# ProProject_Access_Control_USB_Adapter_20.net
KiCad netlist of a schematic drawn in EasyEDA Pro
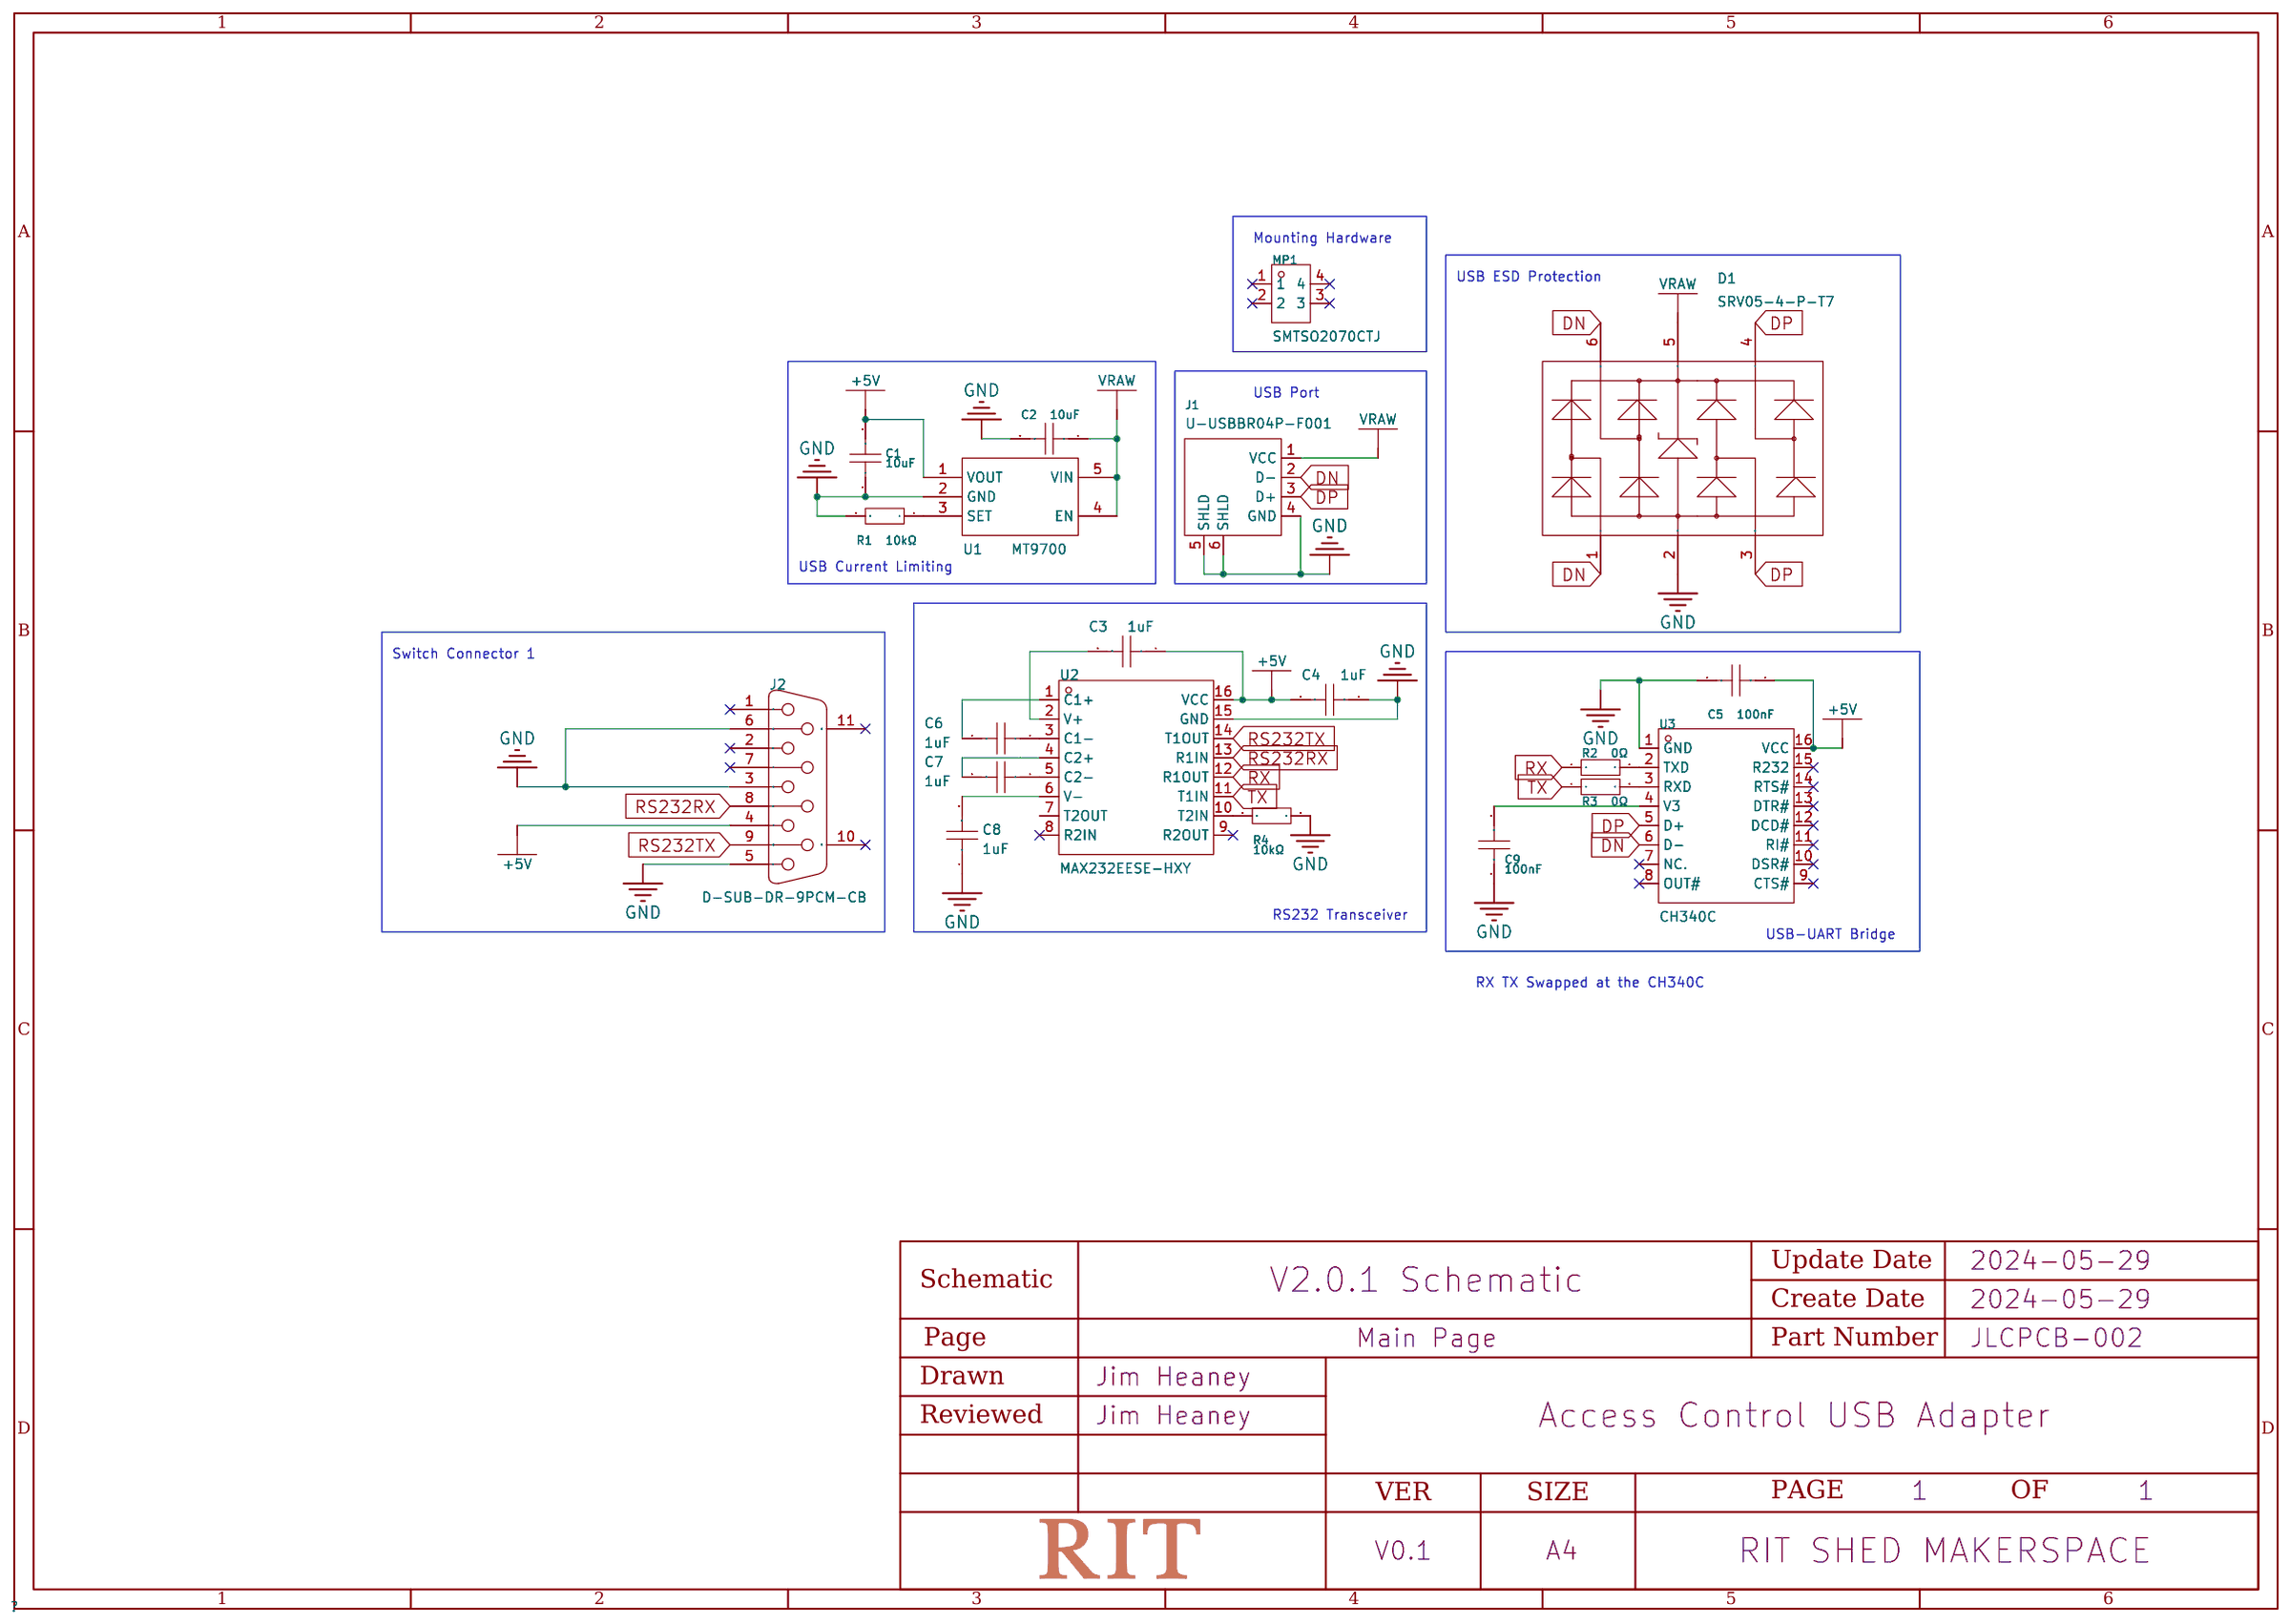
[diagram p0: schematic sheet]

(export (version "E")
  (design (tool "Eeschema 10.0.6"))
  (components
    (comp (ref "C1")
      (value "10uF")
      (footprint "easyedapro:C0603")
      (fields
        (field (name "Manufacturer Part") "CL10A106MA8NRNC")
        (field (name "Manufacturer") "SAMSUNG(三星)")
      )
      (libsource (lib "easyedapro") (part "CL10A106MA8NRNC"))
    )
    (comp (ref "C2")
      (value "10uF")
      (footprint "easyedapro:C0603")
      (fields
        (field (name "Manufacturer Part") "CL10A106MA8NRNC")
        (field (name "Manufacturer") "SAMSUNG(三星)")
      )
      (libsource (lib "easyedapro") (part "CL10A106MA8NRNC"))
    )
    (comp (ref "C3")
      (value "1uF")
      (footprint "easyedapro:C0603")
      (fields
        (field (name "Manufacturer Part") "CL10A105KB8NNNC")
        (field (name "Manufacturer") "SAMSUNG(三星)")
      )
      (libsource (lib "easyedapro") (part "CL10A105KB8NNNC"))
    )
    (comp (ref "C4")
      (value "1uF")
      (footprint "easyedapro:C0603")
      (fields
        (field (name "Manufacturer Part") "CL10A105KB8NNNC")
        (field (name "Manufacturer") "SAMSUNG(三星)")
      )
      (libsource (lib "easyedapro") (part "CL10A105KB8NNNC"))
    )
    (comp (ref "C5")
      (value "100nF")
      (footprint "easyedapro:C0603")
      (fields
        (field (name "Manufacturer Part") "CC0603KRX7R9BB104")
        (field (name "Manufacturer") "YAGEO(国巨)")
      )
      (libsource (lib "easyedapro") (part "CC0603KRX7R9BB104"))
    )
    (comp (ref "C6")
      (value "1uF")
      (footprint "easyedapro:C0603")
      (fields
        (field (name "Manufacturer Part") "CL10A105KB8NNNC")
        (field (name "Manufacturer") "SAMSUNG(三星)")
      )
      (libsource (lib "easyedapro") (part "CL10A105KB8NNNC"))
    )
    (comp (ref "C7")
      (value "1uF")
      (footprint "easyedapro:C0603")
      (fields
        (field (name "Manufacturer Part") "CL10A105KB8NNNC")
        (field (name "Manufacturer") "SAMSUNG(三星)")
      )
      (libsource (lib "easyedapro") (part "CL10A105KB8NNNC"))
    )
    (comp (ref "C8")
      (value "1uF")
      (footprint "easyedapro:C0603")
      (fields
        (field (name "Manufacturer Part") "CL10A105KB8NNNC")
        (field (name "Manufacturer") "SAMSUNG(三星)")
      )
      (libsource (lib "easyedapro") (part "CL10A105KB8NNNC"))
    )
    (comp (ref "C9")
      (value "100nF")
      (footprint "easyedapro:C0603")
      (fields
        (field (name "Manufacturer Part") "CC0603KRX7R9BB104")
        (field (name "Manufacturer") "YAGEO(国巨)")
      )
      (libsource (lib "easyedapro") (part "CC0603KRX7R9BB104"))
    )
    (comp (ref "D1")
      (value "SRV05-4-P-T7")
      (footprint "easyedapro:SOT-23-6_L2.9-W1.6-P0.95-LS2.8-BR")
      (fields (field (name "Manufacturer") "PROTEK"))
      (libsource (lib "easyedapro") (part "SRV05-4-P-T7"))
    )
    (comp (ref "J1")
      (value "U-USBBR04P-F001")
      (footprint "easyedapro:USB-B-TH_U241-041N-1BR85-1")
      (fields (field (name "Manufacturer") "Ckmtw(灿科盟)"))
      (libsource (lib "easyedapro") (part "U-USBBR04P-F001"))
    )
    (comp (ref "J2")
      (value "D-SUB-DR-9PCM-CB")
      (footprint "easyedapro:DB9-TH_ID09S33E4GV00LF")
      (fields (field (name "Manufacturer") "XUNPU(讯普)"))
      (libsource (lib "easyedapro") (part "D-SUB-DR-9PCM-CB"))
    )
    (comp (ref "MP1")
      (value "SMTSO2070CTJ")
      (footprint "easyedapro:SMD_BD5.6-L5.6-W5.6-D3.6")
      (fields (field (name "Manufacturer") "Sinhoo(雄和远景)"))
      (libsource (lib "easyedapro") (part "SMTSO2070CTJ"))
    )
    (comp (ref "R1")
      (value "10kΩ")
      (footprint "easyedapro:R0603")
      (fields
        (field (name "Manufacturer Part") "0603WAF1002T5E")
        (field (name "Manufacturer") "UNI-ROYAL(厚声)")
      )
      (libsource (lib "easyedapro") (part "0603WAF1002T5E"))
    )
    (comp (ref "R2")
      (value "0Ω")
      (footprint "easyedapro:R1206")
      (fields
        (field (name "Manufacturer Part") "1206W4F0000T5E")
        (field (name "Manufacturer") "UNI-ROYAL(厚声)")
      )
      (libsource (lib "easyedapro") (part "1206W4F0000T5E"))
    )
    (comp (ref "R3")
      (value "0Ω")
      (footprint "easyedapro:R1206")
      (fields
        (field (name "Manufacturer Part") "1206W4F0000T5E")
        (field (name "Manufacturer") "UNI-ROYAL(厚声)")
      )
      (libsource (lib "easyedapro") (part "1206W4F0000T5E"))
    )
    (comp (ref "R4")
      (value "10kΩ")
      (footprint "easyedapro:R0603")
      (fields
        (field (name "Manufacturer Part") "0603WAF1002T5E")
        (field (name "Manufacturer") "UNI-ROYAL(厚声)")
      )
      (libsource (lib "easyedapro") (part "0603WAF1002T5E"))
    )
    (comp (ref "U1")
      (value "MT9700")
      (footprint "easyedapro:SOT-23-5_L3.0-W1.7-P0.95-LS2.8-BR")
      (fields (field (name "Manufacturer") "西安航天民芯"))
      (libsource (lib "easyedapro") (part "MT9700"))
    )
    (comp (ref "U2")
      (value "MAX232EESE-HXY")
      (footprint "easyedapro:SOP-16_L9.9-W3.9-P1.27-LS6.0-BL")
      (description "Driver/receiver:2/2 Data Rate:120Kbps Data Rate:120Kbps Supply Voltage:5V Supply Voltage:5V")
      (fields (field (name "Manufacturer") "HXY MOSFET(华轩阳电子)"))
      (libsource (lib "easyedapro") (part "MAX232EESE-HXY"))
    )
    (comp (ref "U3")
      (value "CH340C")
      (footprint "easyedapro:SOP-16_L10.0-W3.9-P1.27-LS6.0-BL")
      (fields (field (name "Manufacturer") "WCH(南京沁恒)"))
      (libsource (lib "easyedapro") (part "CH340C"))
    )
  )
  (nets
    (net (code "1") (name "+5V") (class "Default")
      (node (ref "C1") (pin "2") (pinfunction "2_2") (pintype "input"))
      (node (ref "C3") (pin "1") (pinfunction "1_1") (pintype "unspecified"))
      (node (ref "C4") (pin "2") (pinfunction "2_2") (pintype "unspecified"))
      (node (ref "C5") (pin "2") (pinfunction "2_2") (pintype "input"))
      (node (ref "J2") (pin "4") (pinfunction "4_4") (pintype "input"))
      (node (ref "U1") (pin "1") (pinfunction "VOUT_1") (pintype "unspecified"))
      (node (ref "U2") (pin "16") (pinfunction "VCC_16") (pintype "unspecified"))
      (node (ref "U3") (pin "16") (pinfunction "VCC_16") (pintype "input"))
    )
    (net (code "2") (name "DN") (class "Default")
      (node (ref "D1") (pin "1") (pinfunction "1_1") (pintype "input"))
      (node (ref "D1") (pin "6") (pinfunction "6_6") (pintype "input"))
      (node (ref "J1") (pin "2") (pinfunction "D-_2") (pintype "input"))
      (node (ref "U3") (pin "6") (pinfunction "D-_6") (pintype "input"))
    )
    (net (code "3") (name "DP") (class "Default")
      (node (ref "D1") (pin "3") (pinfunction "3_3") (pintype "input"))
      (node (ref "D1") (pin "4") (pinfunction "4_4") (pintype "input"))
      (node (ref "J1") (pin "3") (pinfunction "D+_3") (pintype "input"))
      (node (ref "U3") (pin "5") (pinfunction "D+_5") (pintype "input"))
    )
    (net (code "4") (name "GND") (class "Default")
      (node (ref "C1") (pin "1") (pinfunction "1_1") (pintype "input"))
      (node (ref "C2") (pin "2") (pinfunction "2_2") (pintype "input"))
      (node (ref "C4") (pin "1") (pinfunction "1_1") (pintype "unspecified"))
      (node (ref "C5") (pin "1") (pinfunction "1_1") (pintype "input"))
      (node (ref "C8") (pin "1") (pinfunction "1_1") (pintype "unspecified"))
      (node (ref "C9") (pin "1") (pinfunction "1_1") (pintype "input"))
      (node (ref "D1") (pin "2") (pinfunction "2_2") (pintype "input"))
      (node (ref "J1") (pin "4") (pinfunction "GND_4") (pintype "input"))
      (node (ref "J1") (pin "5") (pinfunction "SHLD_5") (pintype "input"))
      (node (ref "J1") (pin "6") (pinfunction "SHLD_6") (pintype "input"))
      (node (ref "J2") (pin "3") (pinfunction "3_3") (pintype "input"))
      (node (ref "J2") (pin "5") (pinfunction "5_5") (pintype "input"))
      (node (ref "J2") (pin "6") (pinfunction "6_6") (pintype "input"))
      (node (ref "R1") (pin "2") (pinfunction "2_2") (pintype "input"))
      (node (ref "R4") (pin "1") (pinfunction "1_1") (pintype "input"))
      (node (ref "U1") (pin "2") (pinfunction "GND_2") (pintype "unspecified"))
      (node (ref "U2") (pin "15") (pinfunction "GND_15") (pintype "unspecified"))
      (node (ref "U3") (pin "1") (pinfunction "GND_1") (pintype "input"))
    )
    (net (code "5") (name "Net-(U1-SET)") (class "Default")
      (node (ref "R1") (pin "1") (pinfunction "1_1") (pintype "input"))
      (node (ref "U1") (pin "3") (pinfunction "SET_3") (pintype "unspecified"))
    )
    (net (code "6") (name "Net-(U2-C1+)") (class "Default")
      (node (ref "C6") (pin "2") (pinfunction "2_2") (pintype "unspecified"))
      (node (ref "U2") (pin "1") (pinfunction "C1+_1") (pintype "unspecified"))
    )
    (net (code "7") (name "Net-(U2-C1-)") (class "Default")
      (node (ref "C6") (pin "1") (pinfunction "1_1") (pintype "unspecified"))
      (node (ref "U2") (pin "3") (pinfunction "C1-_3") (pintype "unspecified"))
    )
    (net (code "8") (name "Net-(U2-C2+)") (class "Default")
      (node (ref "C7") (pin "2") (pinfunction "2_2") (pintype "unspecified"))
      (node (ref "U2") (pin "4") (pinfunction "C2+_4") (pintype "unspecified"))
    )
    (net (code "9") (name "Net-(U2-C2-)") (class "Default")
      (node (ref "C7") (pin "1") (pinfunction "1_1") (pintype "unspecified"))
      (node (ref "U2") (pin "5") (pinfunction "C2-_5") (pintype "unspecified"))
    )
    (net (code "10") (name "Net-(U2-T2IN)") (class "Default")
      (node (ref "R4") (pin "2") (pinfunction "2_2") (pintype "input"))
      (node (ref "U2") (pin "10") (pinfunction "T2IN_10") (pintype "unspecified"))
    )
    (net (code "11") (name "Net-(U2-V+)") (class "Default")
      (node (ref "C3") (pin "2") (pinfunction "2_2") (pintype "unspecified"))
      (node (ref "U2") (pin "2") (pinfunction "V+_2") (pintype "unspecified"))
    )
    (net (code "12") (name "Net-(U2-V-)") (class "Default")
      (node (ref "C8") (pin "2") (pinfunction "2_2") (pintype "unspecified"))
      (node (ref "U2") (pin "6") (pinfunction "V-_6") (pintype "unspecified"))
    )
    (net (code "13") (name "Net-(U3-RXD)") (class "Default")
      (node (ref "R3") (pin "2") (pinfunction "2_2") (pintype "input"))
      (node (ref "U3") (pin "3") (pinfunction "RXD_3") (pintype "input"))
    )
    (net (code "14") (name "Net-(U3-TXD)") (class "Default")
      (node (ref "R2") (pin "2") (pinfunction "2_2") (pintype "input"))
      (node (ref "U3") (pin "2") (pinfunction "TXD_2") (pintype "input"))
    )
    (net (code "15") (name "Net-(U3-V3)") (class "Default")
      (node (ref "C9") (pin "2") (pinfunction "2_2") (pintype "input"))
      (node (ref "U3") (pin "4") (pinfunction "V3_4") (pintype "input"))
    )
    (net (code "16") (name "RS232RX") (class "Default")
      (node (ref "J2") (pin "8") (pinfunction "8_8") (pintype "input"))
      (node (ref "U2") (pin "13") (pinfunction "R1IN_13") (pintype "unspecified"))
    )
    (net (code "17") (name "RS232TX") (class "Default")
      (node (ref "J2") (pin "9") (pinfunction "9_9") (pintype "input"))
      (node (ref "U2") (pin "14") (pinfunction "T1OUT_14") (pintype "unspecified"))
    )
    (net (code "18") (name "RX") (class "Default")
      (node (ref "R2") (pin "1") (pinfunction "1_1") (pintype "input"))
      (node (ref "U2") (pin "12") (pinfunction "R1OUT_12") (pintype "unspecified"))
    )
    (net (code "19") (name "TX") (class "Default")
      (node (ref "R3") (pin "1") (pinfunction "1_1") (pintype "input"))
      (node (ref "U2") (pin "11") (pinfunction "T1IN_11") (pintype "unspecified"))
    )
    (net (code "20") (name "VRAW") (class "Default")
      (node (ref "C2") (pin "1") (pinfunction "1_1") (pintype "input"))
      (node (ref "D1") (pin "5") (pinfunction "5_5") (pintype "input"))
      (node (ref "J1") (pin "1") (pinfunction "VCC_1") (pintype "input"))
      (node (ref "U1") (pin "4") (pinfunction "EN_4") (pintype "unspecified"))
      (node (ref "U1") (pin "5") (pinfunction "VIN_5") (pintype "unspecified"))
    )
    (net (code "21") (name "unconnected-(J2-MH1-Pad10)") (class "Default")
      (node (ref "J2") (pin "10") (pinfunction "MH1_10") (pintype "input+no_connect"))
    )
    (net (code "22") (name "unconnected-(J2-MH2-Pad11)") (class "Default")
      (node (ref "J2") (pin "11") (pinfunction "MH2_11") (pintype "input+no_connect"))
    )
    (net (code "23") (name "unconnected-(J2-Pad1)") (class "Default")
      (node (ref "J2") (pin "1") (pinfunction "1_1") (pintype "input+no_connect"))
    )
    (net (code "24") (name "unconnected-(J2-Pad2)") (class "Default")
      (node (ref "J2") (pin "2") (pinfunction "2_2") (pintype "input+no_connect"))
    )
    (net (code "25") (name "unconnected-(J2-Pad7)") (class "Default")
      (node (ref "J2") (pin "7") (pinfunction "7_7") (pintype "input+no_connect"))
    )
    (net (code "26") (name "unconnected-(MP1-Pad1)") (class "Default")
      (node (ref "MP1") (pin "1") (pinfunction "1_1") (pintype "input+no_connect"))
    )
    (net (code "27") (name "unconnected-(MP1-Pad2)") (class "Default")
      (node (ref "MP1") (pin "2") (pinfunction "2_2") (pintype "input+no_connect"))
    )
    (net (code "28") (name "unconnected-(MP1-Pad3)") (class "Default")
      (node (ref "MP1") (pin "3") (pinfunction "3_3") (pintype "input+no_connect"))
    )
    (net (code "29") (name "unconnected-(MP1-Pad4)") (class "Default")
      (node (ref "MP1") (pin "4") (pinfunction "4_4") (pintype "input+no_connect"))
    )
    (net (code "30") (name "unconnected-(U2-R2IN-Pad8)") (class "Default")
      (node (ref "U2") (pin "8") (pinfunction "R2IN_8") (pintype "unspecified+no_connect"))
    )
    (net (code "31") (name "unconnected-(U2-R2OUT-Pad9)") (class "Default")
      (node (ref "U2") (pin "9") (pinfunction "R2OUT_9") (pintype "unspecified+no_connect"))
    )
    (net (code "32") (name "unconnected-(U2-T2OUT-Pad7)") (class "Default")
      (node (ref "U2") (pin "7") (pinfunction "T2OUT_7") (pintype "unspecified"))
    )
    (net (code "33") (name "unconnected-(U3-CTS#-Pad9)") (class "Default")
      (node (ref "U3") (pin "9") (pinfunction "CTS#_9") (pintype "input+no_connect"))
    )
    (net (code "34") (name "unconnected-(U3-DCD#-Pad12)") (class "Default")
      (node (ref "U3") (pin "12") (pinfunction "DCD#_12") (pintype "input+no_connect"))
    )
    (net (code "35") (name "unconnected-(U3-DSR#-Pad10)") (class "Default")
      (node (ref "U3") (pin "10") (pinfunction "DSR#_10") (pintype "input+no_connect"))
    )
    (net (code "36") (name "unconnected-(U3-DTR#-Pad13)") (class "Default")
      (node (ref "U3") (pin "13") (pinfunction "DTR#_13") (pintype "input+no_connect"))
    )
    (net (code "37") (name "unconnected-(U3-NC.-Pad7)") (class "Default")
      (node (ref "U3") (pin "7") (pinfunction "NC._7") (pintype "input+no_connect"))
    )
    (net (code "38") (name "unconnected-(U3-OUT#-Pad8)") (class "Default")
      (node (ref "U3") (pin "8") (pinfunction "OUT#_8") (pintype "input+no_connect"))
    )
    (net (code "39") (name "unconnected-(U3-R232-Pad15)") (class "Default")
      (node (ref "U3") (pin "15") (pinfunction "R232_15") (pintype "input+no_connect"))
    )
    (net (code "40") (name "unconnected-(U3-RI#-Pad11)") (class "Default")
      (node (ref "U3") (pin "11") (pinfunction "RI#_11") (pintype "input+no_connect"))
    )
    (net (code "41") (name "unconnected-(U3-RTS#-Pad14)") (class "Default")
      (node (ref "U3") (pin "14") (pinfunction "RTS#_14") (pintype "input+no_connect"))
    )
  )
)
